# InductionSensorBoardForOxCNC_v2.net
KiCad netlist of a schematic drawn in EAGLE
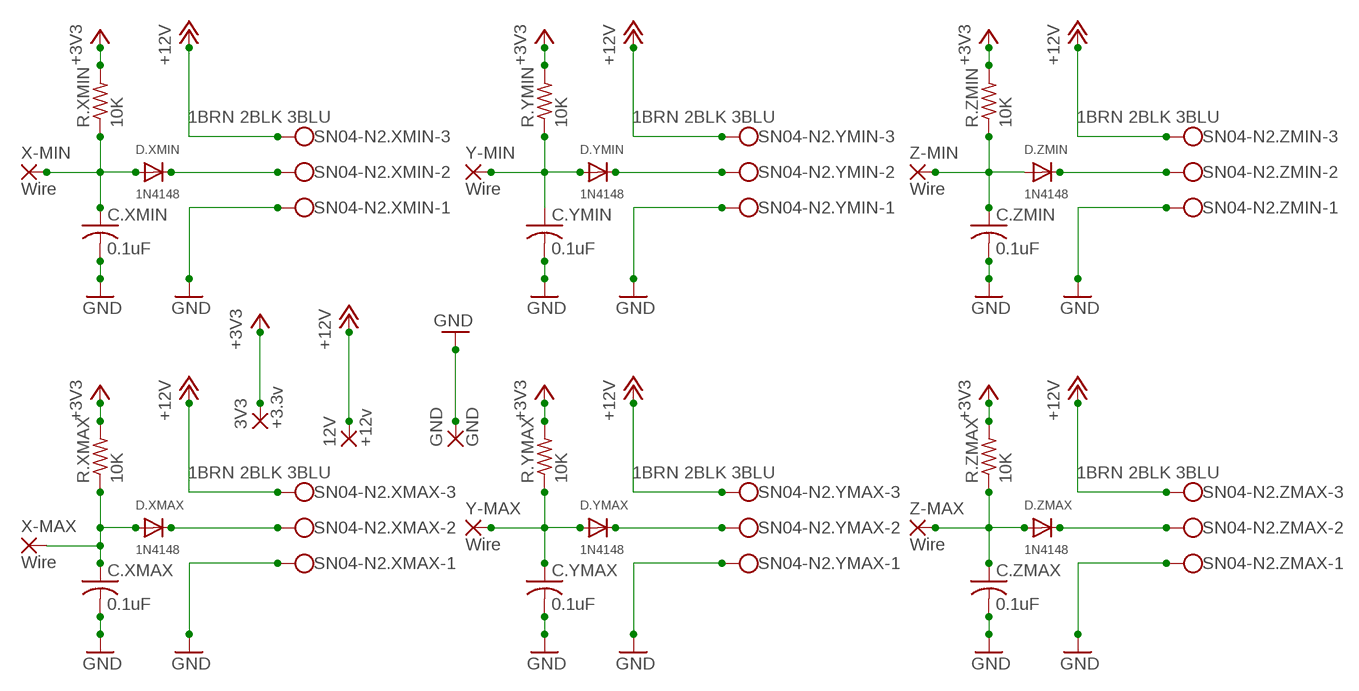
[diagram p0: schematic, sheet 1]

(export (version "E")
  (design (tool "Eeschema 10.0.6"))
  (components
    (comp (ref "3V3")
      (value "+3.3v")
      (footprint "eagle-import:3,81_1,4")
      (libsource (lib "eagle-import") (part "3,81/1,4"))
    )
    (comp (ref "12V")
      (value "+12v")
      (footprint "eagle-import:3,81_1,4")
      (libsource (lib "eagle-import") (part "3,81/1,4"))
    )
    (comp (ref "C.XMAX")
      (value "0.1uF")
      (footprint "eagle-import:C050-024X044")
      (libsource (lib "eagle-import") (part "C-US050-024X044"))
    )
    (comp (ref "C.XMIN")
      (value "0.1uF")
      (footprint "eagle-import:C050-024X044")
      (libsource (lib "eagle-import") (part "C-US050-024X044"))
    )
    (comp (ref "C.YMAX")
      (value "0.1uF")
      (footprint "eagle-import:C050-024X044")
      (libsource (lib "eagle-import") (part "C-US050-024X044"))
    )
    (comp (ref "C.YMIN")
      (value "0.1uF")
      (footprint "eagle-import:C050-024X044")
      (libsource (lib "eagle-import") (part "C-US050-024X044"))
    )
    (comp (ref "C.ZMAX")
      (value "0.1uF")
      (footprint "eagle-import:C050-024X044")
      (libsource (lib "eagle-import") (part "C-US050-024X044"))
    )
    (comp (ref "C.ZMIN")
      (value "0.1uF")
      (footprint "eagle-import:C050-024X044")
      (libsource (lib "eagle-import") (part "C-US050-024X044"))
    )
    (comp (ref "D.XMAX")
      (value "1N4148")
      (footprint "eagle-import:DO-1N4148")
      (libsource (lib "eagle-import") (part "DIODEDO-1N4148"))
    )
    (comp (ref "D.XMIN")
      (value "1N4148")
      (footprint "eagle-import:DO-1N4148")
      (libsource (lib "eagle-import") (part "DIODEDO-1N4148"))
    )
    (comp (ref "D.YMAX")
      (value "1N4148")
      (footprint "eagle-import:DO-1N4148")
      (libsource (lib "eagle-import") (part "DIODEDO-1N4148"))
    )
    (comp (ref "D.YMIN")
      (value "1N4148")
      (footprint "eagle-import:DO-1N4148")
      (libsource (lib "eagle-import") (part "DIODEDO-1N4148"))
    )
    (comp (ref "D.ZMAX")
      (value "1N4148")
      (footprint "eagle-import:DO-1N4148")
      (libsource (lib "eagle-import") (part "DIODEDO-1N4148"))
    )
    (comp (ref "D.ZMIN")
      (value "1N4148")
      (footprint "eagle-import:DO-1N4148")
      (libsource (lib "eagle-import") (part "DIODEDO-1N4148"))
    )
    (comp (ref "GND")
      (value "GND")
      (footprint "eagle-import:3,81_1,4")
      (libsource (lib "eagle-import") (part "3,81/1,4"))
    )
    (comp (ref "R.XMAX")
      (value "10K")
      (footprint "eagle-import:0207_10")
      (libsource (lib "eagle-import") (part "R-US_0207/10"))
    )
    (comp (ref "R.XMIN")
      (value "10K")
      (footprint "eagle-import:0207_10")
      (libsource (lib "eagle-import") (part "R-US_0207/10"))
    )
    (comp (ref "R.YMAX")
      (value "10K")
      (footprint "eagle-import:0207_10")
      (libsource (lib "eagle-import") (part "R-US_0207/10"))
    )
    (comp (ref "R.YMIN")
      (value "10K")
      (footprint "eagle-import:0207_10")
      (libsource (lib "eagle-import") (part "R-US_0207/10"))
    )
    (comp (ref "R.ZMAX")
      (value "10K")
      (footprint "eagle-import:0207_10")
      (libsource (lib "eagle-import") (part "R-US_0207/10"))
    )
    (comp (ref "R.ZMIN")
      (value "10K")
      (footprint "eagle-import:0207_10")
      (libsource (lib "eagle-import") (part "R-US_0207/10"))
    )
    (comp (ref "SN04-N2.XMAX")
      (value "1BRN 2BLK 3BLU")
      (footprint "eagle-import:W237-103")
      (fields (field (name "MPN") "237-103"))
      (libsource (lib "eagle-import") (part "W237-103"))
    )
    (comp (ref "SN04-N2.XMIN")
      (value "1BRN 2BLK 3BLU")
      (footprint "eagle-import:W237-103")
      (fields (field (name "MPN") "237-103"))
      (libsource (lib "eagle-import") (part "W237-103"))
    )
    (comp (ref "SN04-N2.YMAX")
      (value "1BRN 2BLK 3BLU")
      (footprint "eagle-import:W237-103")
      (fields (field (name "MPN") "237-103"))
      (libsource (lib "eagle-import") (part "W237-103"))
    )
    (comp (ref "SN04-N2.YMIN")
      (value "1BRN 2BLK 3BLU")
      (footprint "eagle-import:W237-103")
      (fields (field (name "MPN") "237-103"))
      (libsource (lib "eagle-import") (part "W237-103"))
    )
    (comp (ref "SN04-N2.ZMAX")
      (value "1BRN 2BLK 3BLU")
      (footprint "eagle-import:W237-103")
      (fields (field (name "MPN") "237-103"))
      (libsource (lib "eagle-import") (part "W237-103"))
    )
    (comp (ref "SN04-N2.ZMIN")
      (value "1BRN 2BLK 3BLU")
      (footprint "eagle-import:W237-103")
      (fields (field (name "MPN") "237-103"))
      (libsource (lib "eagle-import") (part "W237-103"))
    )
    (comp (ref "X-MAX")
      (value "Wire")
      (footprint "eagle-import:3,81_1,1")
      (libsource (lib "eagle-import") (part "3,81/1,1"))
    )
    (comp (ref "X-MIN")
      (value "Wire")
      (footprint "eagle-import:3,81_1,1")
      (libsource (lib "eagle-import") (part "3,81/1,1"))
    )
    (comp (ref "Y-MAX")
      (value "Wire")
      (footprint "eagle-import:3,81_1,1")
      (libsource (lib "eagle-import") (part "3,81/1,1"))
    )
    (comp (ref "Y-MIN")
      (value "Wire")
      (footprint "eagle-import:3,81_1,1")
      (libsource (lib "eagle-import") (part "3,81/1,1"))
    )
    (comp (ref "Z-MAX")
      (value "Wire")
      (footprint "eagle-import:3,81_1,1")
      (libsource (lib "eagle-import") (part "3,81/1,1"))
    )
    (comp (ref "Z-MIN")
      (value "Wire")
      (footprint "eagle-import:3,81_1,1")
      (libsource (lib "eagle-import") (part "3,81/1,1"))
    )
  )
  (nets
    (net (code "1") (name "+3V3") (class "Default")
      (node (ref "3V3") (pin "1") (pinfunction "P_1") (pintype "passive"))
      (node (ref "R.XMAX") (pin "2") (pinfunction "2_2") (pintype "passive"))
      (node (ref "R.XMIN") (pin "2") (pinfunction "2_2") (pintype "passive"))
      (node (ref "R.YMAX") (pin "2") (pinfunction "2_2") (pintype "passive"))
      (node (ref "R.YMIN") (pin "2") (pinfunction "2_2") (pintype "passive"))
      (node (ref "R.ZMAX") (pin "2") (pinfunction "2_2") (pintype "passive"))
      (node (ref "R.ZMIN") (pin "2") (pinfunction "2_2") (pintype "passive"))
    )
    (net (code "2") (name "+12V") (class "Default")
      (node (ref "12V") (pin "1") (pinfunction "P_1") (pintype "passive"))
      (node (ref "SN04-N2.XMAX") (pin "3") (pinfunction "KL_3") (pintype "passive"))
      (node (ref "SN04-N2.XMIN") (pin "3") (pinfunction "KL_3") (pintype "passive"))
      (node (ref "SN04-N2.YMAX") (pin "3") (pinfunction "KL_3") (pintype "passive"))
      (node (ref "SN04-N2.YMIN") (pin "3") (pinfunction "KL_3") (pintype "passive"))
      (node (ref "SN04-N2.ZMAX") (pin "3") (pinfunction "KL_3") (pintype "passive"))
      (node (ref "SN04-N2.ZMIN") (pin "3") (pinfunction "KL_3") (pintype "passive"))
    )
    (net (code "3") (name "GND") (class "Default")
      (node (ref "C.XMAX") (pin "2") (pinfunction "2_2") (pintype "passive"))
      (node (ref "C.XMIN") (pin "2") (pinfunction "2_2") (pintype "passive"))
      (node (ref "C.YMAX") (pin "2") (pinfunction "2_2") (pintype "passive"))
      (node (ref "C.YMIN") (pin "2") (pinfunction "2_2") (pintype "passive"))
      (node (ref "C.ZMAX") (pin "2") (pinfunction "2_2") (pintype "passive"))
      (node (ref "C.ZMIN") (pin "2") (pinfunction "2_2") (pintype "passive"))
      (node (ref "GND") (pin "1") (pinfunction "P_1") (pintype "passive"))
      (node (ref "SN04-N2.XMAX") (pin "1") (pinfunction "KL_1") (pintype "passive"))
      (node (ref "SN04-N2.XMIN") (pin "1") (pinfunction "KL_1") (pintype "passive"))
      (node (ref "SN04-N2.YMAX") (pin "1") (pinfunction "KL_1") (pintype "passive"))
      (node (ref "SN04-N2.YMIN") (pin "1") (pinfunction "KL_1") (pintype "passive"))
      (node (ref "SN04-N2.ZMAX") (pin "1") (pinfunction "KL_1") (pintype "passive"))
      (node (ref "SN04-N2.ZMIN") (pin "1") (pinfunction "KL_1") (pintype "passive"))
    )
    (net (code "4") (name "Net-(SN04-N2.XMAXB-KL)") (class "Default")
      (node (ref "D.XMAX") (pin "C") (pinfunction "C_C") (pintype "passive"))
      (node (ref "SN04-N2.XMAX") (pin "2") (pinfunction "KL_2") (pintype "passive"))
    )
    (net (code "5") (name "Net-(SN04-N2.XMINB-KL)") (class "Default")
      (node (ref "D.XMIN") (pin "C") (pinfunction "C_C") (pintype "passive"))
      (node (ref "SN04-N2.XMIN") (pin "2") (pinfunction "KL_2") (pintype "passive"))
    )
    (net (code "6") (name "Net-(SN04-N2.YMAXB-KL)") (class "Default")
      (node (ref "D.YMAX") (pin "C") (pinfunction "C_C") (pintype "passive"))
      (node (ref "SN04-N2.YMAX") (pin "2") (pinfunction "KL_2") (pintype "passive"))
    )
    (net (code "7") (name "Net-(SN04-N2.YMINB-KL)") (class "Default")
      (node (ref "D.YMIN") (pin "C") (pinfunction "C_C") (pintype "passive"))
      (node (ref "SN04-N2.YMIN") (pin "2") (pinfunction "KL_2") (pintype "passive"))
    )
    (net (code "8") (name "Net-(SN04-N2.ZMAXB-KL)") (class "Default")
      (node (ref "D.ZMAX") (pin "C") (pinfunction "C_C") (pintype "passive"))
      (node (ref "SN04-N2.ZMAX") (pin "2") (pinfunction "KL_2") (pintype "passive"))
    )
    (net (code "9") (name "Net-(SN04-N2.ZMINB-KL)") (class "Default")
      (node (ref "D.ZMIN") (pin "C") (pinfunction "C_C") (pintype "passive"))
      (node (ref "SN04-N2.ZMIN") (pin "2") (pinfunction "KL_2") (pintype "passive"))
    )
    (net (code "10") (name "Net-(X-MAX-P)") (class "Default")
      (node (ref "C.XMAX") (pin "1") (pinfunction "1_1") (pintype "passive"))
      (node (ref "D.XMAX") (pin "A") (pinfunction "A_A") (pintype "passive"))
      (node (ref "R.XMAX") (pin "1") (pinfunction "1_1") (pintype "passive"))
      (node (ref "X-MAX") (pin "1") (pinfunction "P_1") (pintype "passive"))
    )
    (net (code "11") (name "Net-(X-MIN-P)") (class "Default")
      (node (ref "C.XMIN") (pin "1") (pinfunction "1_1") (pintype "passive"))
      (node (ref "D.XMIN") (pin "A") (pinfunction "A_A") (pintype "passive"))
      (node (ref "R.XMIN") (pin "1") (pinfunction "1_1") (pintype "passive"))
      (node (ref "X-MIN") (pin "1") (pinfunction "P_1") (pintype "passive"))
    )
    (net (code "12") (name "Net-(Y-MAX-P)") (class "Default")
      (node (ref "C.YMAX") (pin "1") (pinfunction "1_1") (pintype "passive"))
      (node (ref "D.YMAX") (pin "A") (pinfunction "A_A") (pintype "passive"))
      (node (ref "R.YMAX") (pin "1") (pinfunction "1_1") (pintype "passive"))
      (node (ref "Y-MAX") (pin "1") (pinfunction "P_1") (pintype "passive"))
    )
    (net (code "13") (name "Net-(Y-MIN-P)") (class "Default")
      (node (ref "C.YMIN") (pin "1") (pinfunction "1_1") (pintype "passive"))
      (node (ref "D.YMIN") (pin "A") (pinfunction "A_A") (pintype "passive"))
      (node (ref "R.YMIN") (pin "1") (pinfunction "1_1") (pintype "passive"))
      (node (ref "Y-MIN") (pin "1") (pinfunction "P_1") (pintype "passive"))
    )
    (net (code "14") (name "Net-(Z-MAX-P)") (class "Default")
      (node (ref "C.ZMAX") (pin "1") (pinfunction "1_1") (pintype "passive"))
      (node (ref "D.ZMAX") (pin "A") (pinfunction "A_A") (pintype "passive"))
      (node (ref "R.ZMAX") (pin "1") (pinfunction "1_1") (pintype "passive"))
      (node (ref "Z-MAX") (pin "1") (pinfunction "P_1") (pintype "passive"))
    )
    (net (code "15") (name "Net-(Z-MIN-P)") (class "Default")
      (node (ref "C.ZMIN") (pin "1") (pinfunction "1_1") (pintype "passive"))
      (node (ref "D.ZMIN") (pin "A") (pinfunction "A_A") (pintype "passive"))
      (node (ref "R.ZMIN") (pin "1") (pinfunction "1_1") (pintype "passive"))
      (node (ref "Z-MIN") (pin "1") (pinfunction "P_1") (pintype "passive"))
    )
  )
)
